# nawilzacz.net
KiCad netlist of a schematic drawn in EAGLE
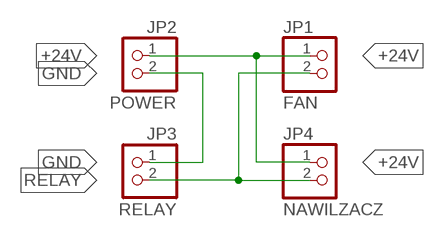
[diagram p0: schematic, sheet 1]

(export (version "E")
  (design (tool "Eeschema 10.0.6"))
  (components
    (comp (ref "JP1")
      (value "FAN")
      (footprint "eagle-import:1X02")
      (libsource (lib "eagle-import") (part "PINHD-1X2"))
    )
    (comp (ref "JP2")
      (value "POWER")
      (footprint "eagle-import:1X02")
      (libsource (lib "eagle-import") (part "PINHD-1X2"))
    )
    (comp (ref "JP3")
      (value "RELAY")
      (footprint "eagle-import:1X02")
      (libsource (lib "eagle-import") (part "PINHD-1X2"))
    )
    (comp (ref "JP4")
      (value "NAWILZACZ")
      (footprint "eagle-import:1X02")
      (libsource (lib "eagle-import") (part "PINHD-1X2"))
    )
  )
  (nets
    (net (code "1") (name "+24V") (class "Default")
      (node (ref "JP1") (pin "1") (pinfunction "1_1") (pintype "passive"))
      (node (ref "JP2") (pin "1") (pinfunction "1_1") (pintype "passive"))
      (node (ref "JP4") (pin "1") (pinfunction "1_1") (pintype "passive"))
    )
    (net (code "2") (name "GND") (class "Default")
      (node (ref "JP2") (pin "2") (pinfunction "2_2") (pintype "passive"))
      (node (ref "JP3") (pin "1") (pinfunction "1_1") (pintype "passive"))
    )
    (net (code "3") (name "RELAY") (class "Default")
      (node (ref "JP1") (pin "2") (pinfunction "2_2") (pintype "passive"))
      (node (ref "JP3") (pin "2") (pinfunction "2_2") (pintype "passive"))
      (node (ref "JP4") (pin "2") (pinfunction "2_2") (pintype "passive"))
    )
  )
)
